# SCH_Moon.net
KiCad netlist of a schematic drawn in EasyEDA
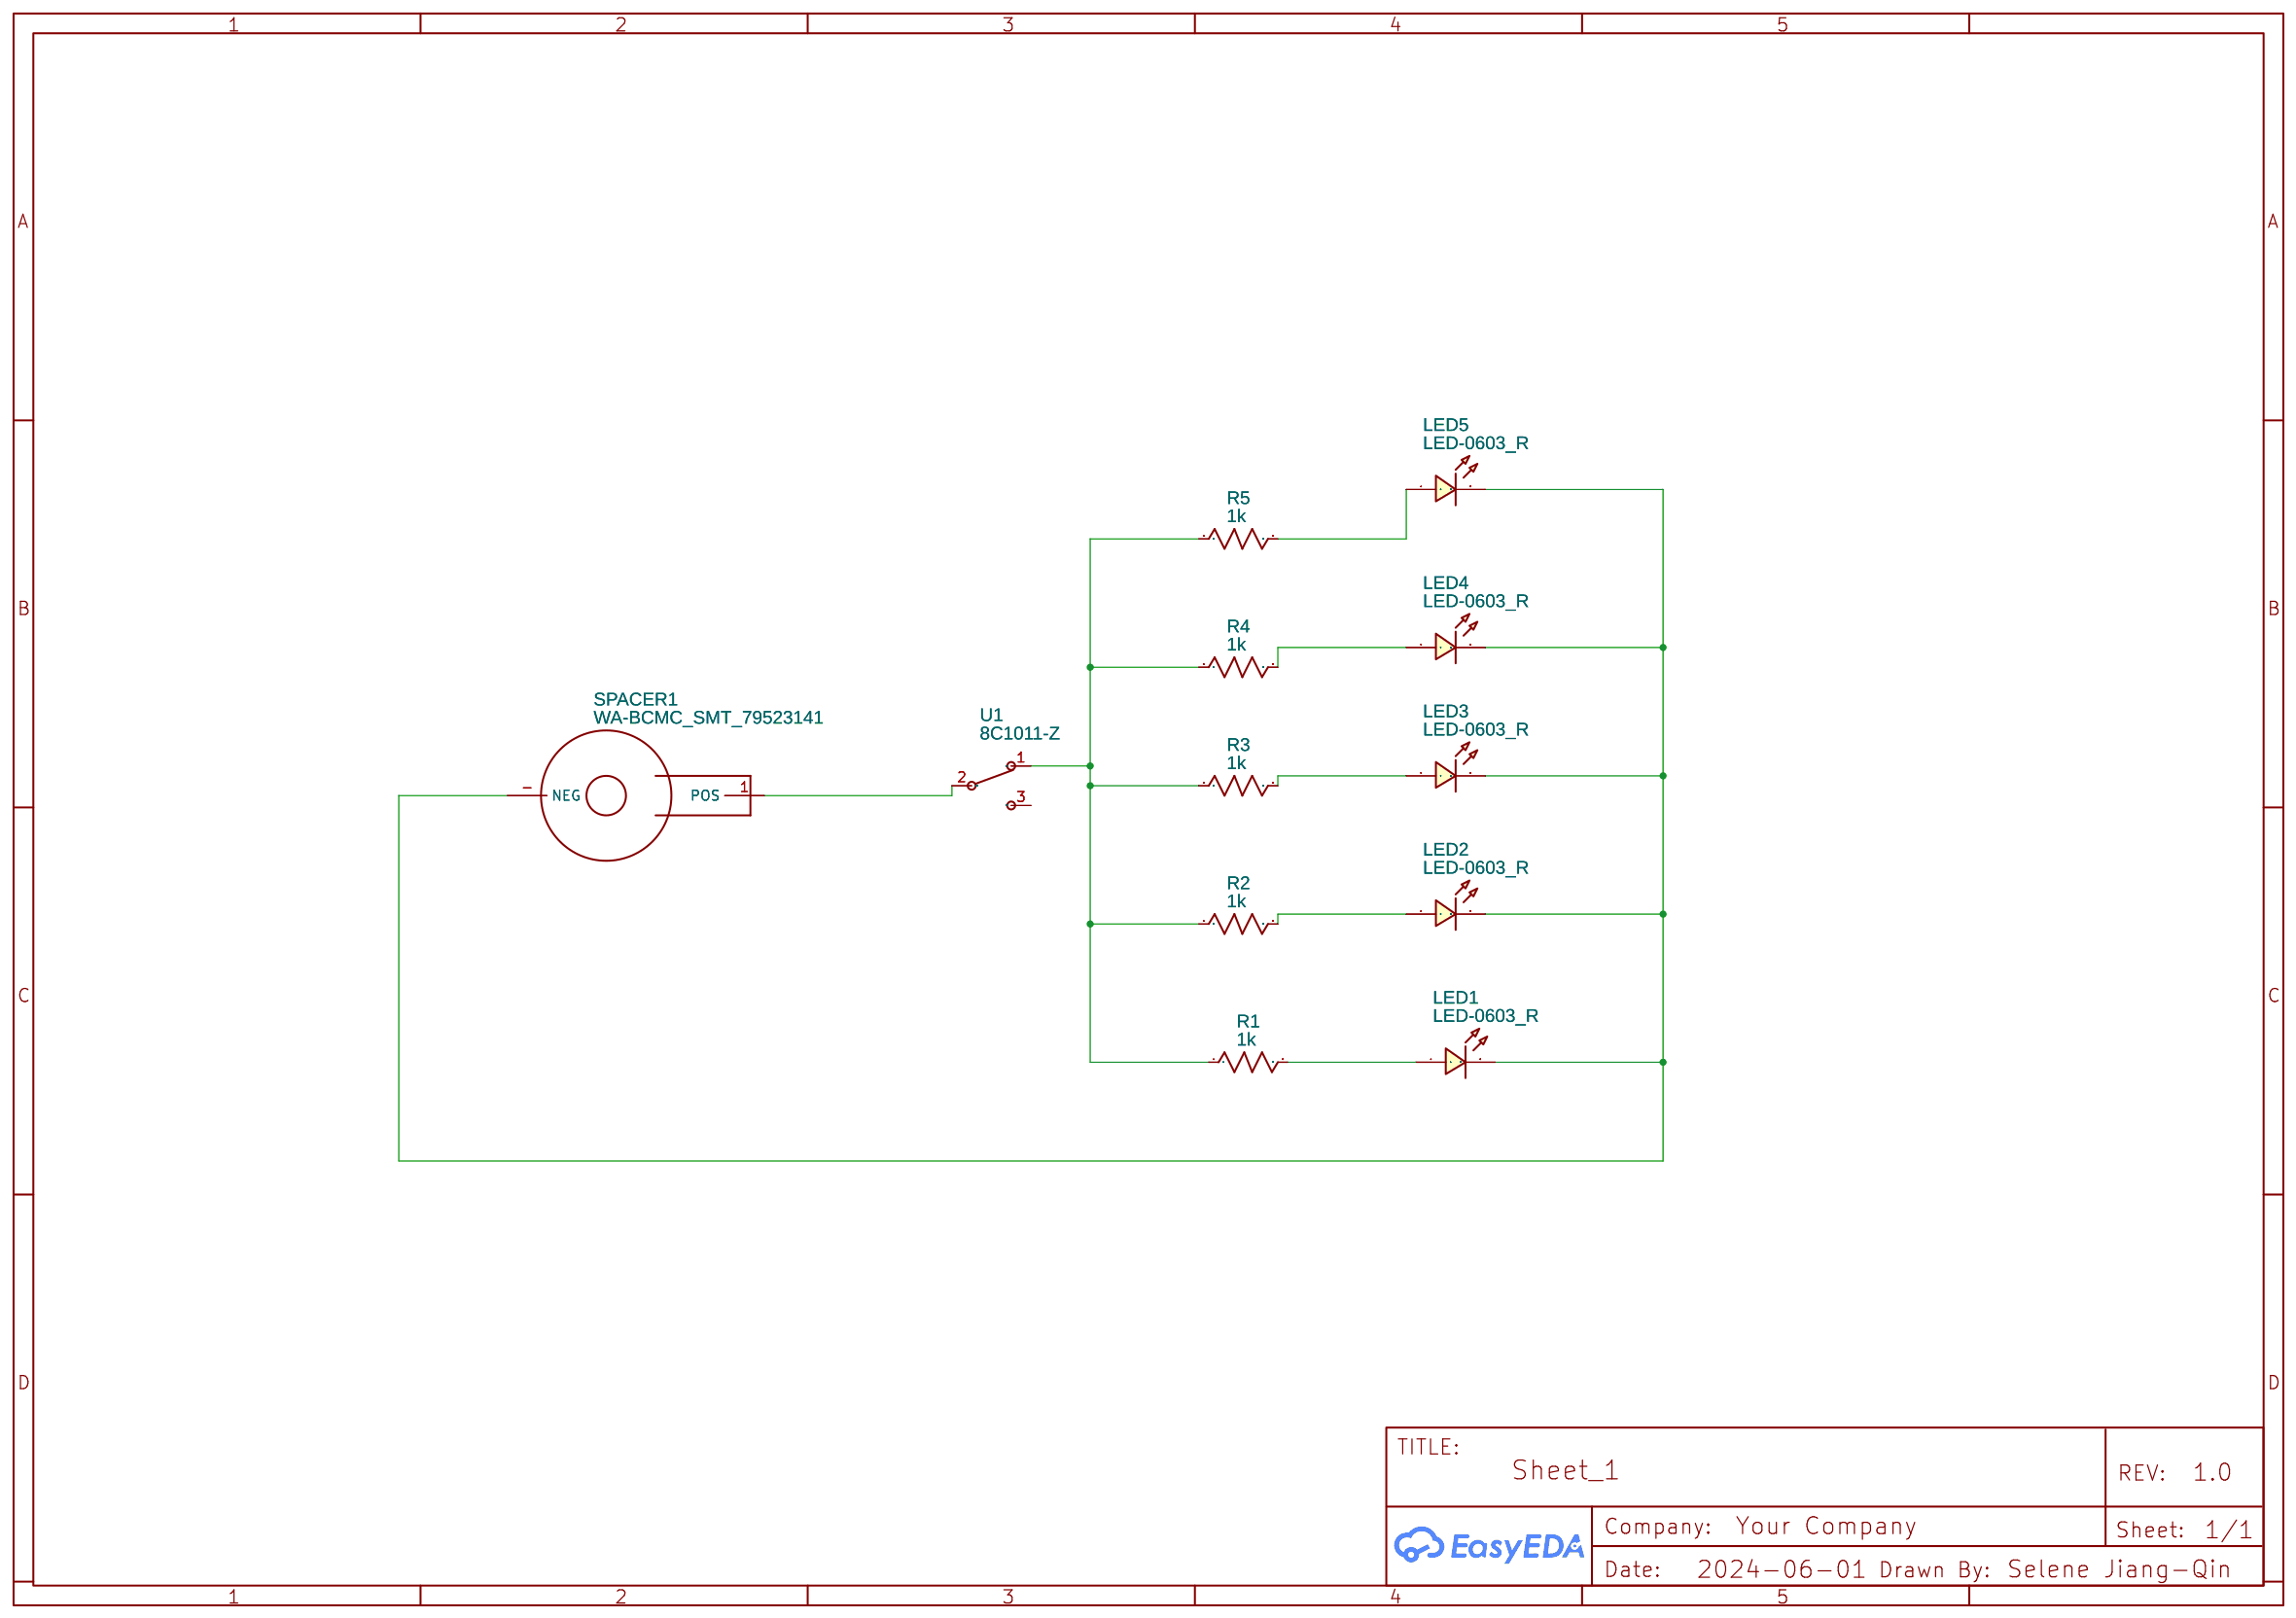
[diagram p0: schematic sheet]

(export (version "E")
  (design (tool "Eeschema 10.0.6"))
  (components
    (comp (ref "LED1")
      (value "LED-0603_R")
      (fields
        (field (name "Manufacturer Part") "19-217/R6C-AL1M2VY/3T")
        (field (name "Manufacturer") "EVERLIGHT(台湾亿光)")
      )
      (libsource (lib "") (part "LED-0603_R"))
    )
    (comp (ref "LED2")
      (value "LED-0603_R")
      (fields
        (field (name "Manufacturer Part") "19-217/R6C-AL1M2VY/3T")
        (field (name "Manufacturer") "EVERLIGHT(台湾亿光)")
      )
      (libsource (lib "") (part "LED-0603_R"))
    )
    (comp (ref "LED3")
      (value "LED-0603_R")
      (fields
        (field (name "Manufacturer Part") "19-217/R6C-AL1M2VY/3T")
        (field (name "Manufacturer") "EVERLIGHT(台湾亿光)")
      )
      (libsource (lib "") (part "LED-0603_R"))
    )
    (comp (ref "LED4")
      (value "LED-0603_R")
      (fields
        (field (name "Manufacturer Part") "19-217/R6C-AL1M2VY/3T")
        (field (name "Manufacturer") "EVERLIGHT(台湾亿光)")
      )
      (libsource (lib "") (part "LED-0603_R"))
    )
    (comp (ref "LED5")
      (value "LED-0603_R")
      (fields
        (field (name "Manufacturer Part") "19-217/R6C-AL1M2VY/3T")
        (field (name "Manufacturer") "EVERLIGHT(台湾亿光)")
      )
      (libsource (lib "") (part "LED-0603_R"))
    )
    (comp (ref "R1") (value "1k") (libsource (lib "") (part "R_0603_US")))
    (comp (ref "R2") (value "1k") (libsource (lib "") (part "R_0603_US")))
    (comp (ref "R3") (value "1k") (libsource (lib "") (part "R_0603_US")))
    (comp (ref "R4") (value "1k") (libsource (lib "") (part "R_0603_US")))
    (comp (ref "R5") (value "1k") (libsource (lib "") (part "R_0603_US")))
    (comp (ref "SPACER1") (value "WA-BCMC_SMT_79523141") (libsource (lib "") (part "WA-BCMC_SMT_79523141")))
    (comp (ref "U1")
      (value "8C1011-Z")
      (fields (field (name "Manufacturer") "NIDEC(尼得科)"))
      (libsource (lib "") (part "8C1011-Z"))
    )
  )
  (nets
    (net (code "1") (name "Net-(LED1-Pad1)") (class "Default")
      (node (ref "LED1") (pin "1") (pinfunction "1_1") (pintype "unspecified"))
      (node (ref "R1") (pin "2") (pinfunction "2_2") (pintype "unspecified"))
    )
    (net (code "2") (name "Net-(LED2-Pad1)") (class "Default")
      (node (ref "LED2") (pin "1") (pinfunction "1_1") (pintype "unspecified"))
      (node (ref "R2") (pin "2") (pinfunction "2_2") (pintype "unspecified"))
    )
    (net (code "3") (name "Net-(LED3-Pad1)") (class "Default")
      (node (ref "LED3") (pin "1") (pinfunction "1_1") (pintype "unspecified"))
      (node (ref "R3") (pin "2") (pinfunction "2_2") (pintype "unspecified"))
    )
    (net (code "4") (name "Net-(LED4-Pad1)") (class "Default")
      (node (ref "LED4") (pin "1") (pinfunction "1_1") (pintype "unspecified"))
      (node (ref "R4") (pin "2") (pinfunction "2_2") (pintype "unspecified"))
    )
    (net (code "5") (name "Net-(LED5-Pad1)") (class "Default")
      (node (ref "LED5") (pin "1") (pinfunction "1_1") (pintype "unspecified"))
      (node (ref "R5") (pin "2") (pinfunction "2_2") (pintype "unspecified"))
    )
    (net (code "6") (name "Net-(SPACER1-NEG)") (class "Default")
      (node (ref "LED1") (pin "2") (pinfunction "2_2") (pintype "unspecified"))
      (node (ref "LED2") (pin "2") (pinfunction "2_2") (pintype "unspecified"))
      (node (ref "LED3") (pin "2") (pinfunction "2_2") (pintype "unspecified"))
      (node (ref "LED4") (pin "2") (pinfunction "2_2") (pintype "unspecified"))
      (node (ref "LED5") (pin "2") (pinfunction "2_2") (pintype "unspecified"))
      (node (ref "SPACER1") (pin "-") (pinfunction "NEG_-") (pintype "unspecified"))
    )
    (net (code "7") (name "Net-(SPACER1-POS)") (class "Default")
      (node (ref "SPACER1") (pin "1") (pinfunction "POS_1") (pintype "unspecified"))
      (node (ref "U1") (pin "2") (pinfunction "COMM_2") (pintype "unspecified"))
    )
    (net (code "8") (name "Net-(U1-ON)") (class "Default")
      (node (ref "R1") (pin "1") (pinfunction "1_1") (pintype "unspecified"))
      (node (ref "R2") (pin "1") (pinfunction "1_1") (pintype "unspecified"))
      (node (ref "R3") (pin "1") (pinfunction "1_1") (pintype "unspecified"))
      (node (ref "R4") (pin "1") (pinfunction "1_1") (pintype "unspecified"))
      (node (ref "R5") (pin "1") (pinfunction "1_1") (pintype "unspecified"))
      (node (ref "U1") (pin "1") (pinfunction "ON_1") (pintype "unspecified"))
    )
    (net (code "9") (name "unconnected-(U1-NC-Pad3)") (class "Default")
      (node (ref "U1") (pin "3") (pinfunction "NC_3") (pintype "unspecified"))
    )
  )
)
